# Sheet1.net
KiCad netlist of a schematic drawn in Altium Designer
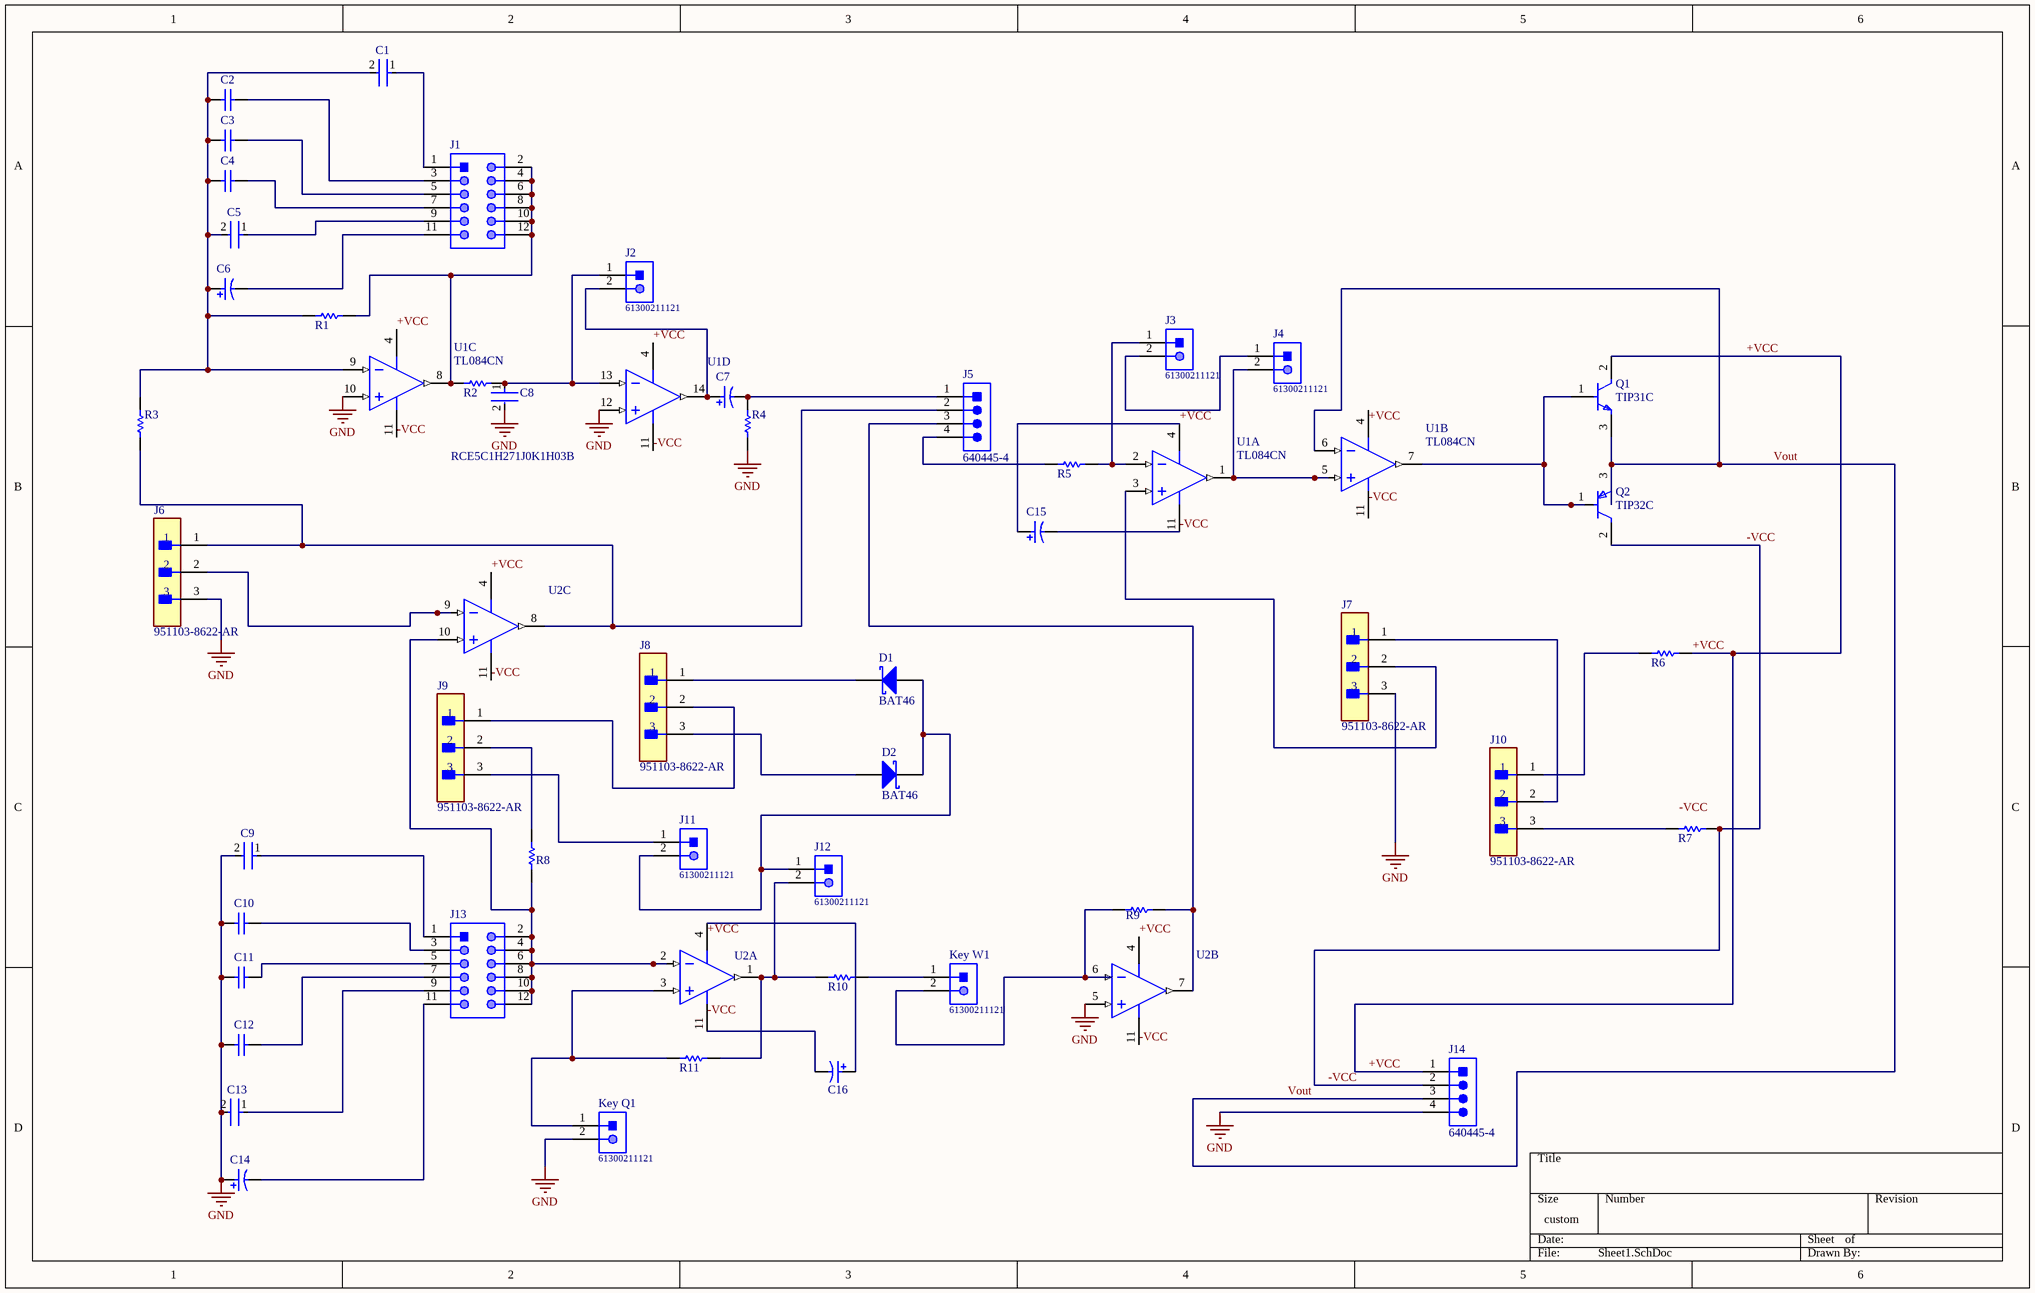
[diagram p0: Sheet1.SchDoc]

(export (version "E")
  (design (tool "Eeschema 10.0.6"))
  (components
    (comp (ref "C1")
      (value "RCE5C1H101J0DBH03A")
      (footprint "FP-RCE0DB-MFG")
      (description "Cap Ceramic 100pF 50V C0G ±5% Radial 2.5mm +125°C Ammo Pack")
      (fields (field (name "TOLERANCE") "5%"))
      (libsource (lib "Altium Content Vault") (part "b4654b650e69147ec39a6b967a45e02"))
    )
    (comp (ref "C2")
      (value "C315C102K1R5TA")
      (footprint "KEMT-C315-THT-2")
      (description "Capacitor, Ceramic, 1000 pF, +/-10 %, 100 V, X7R, -55 to 125 degC, 2-Pin THD, RoHS, Bulk")
      (libsource (lib "Altium Content Vault") (part "CAP-NP-2"))
    )
    (comp (ref "C3")
      (value "C315C103K1R5TA")
      (footprint "KEMT-C315-THT-2")
      (description "Capacitor, Ceramic, 0.01 uF, +/- 10%, 100 V, X7R, -55 to 125 degC, 2-Pin THD, RoHS, Bulk")
      (libsource (lib "Altium Content Vault") (part "CAP-NP-2"))
    )
    (comp (ref "C4")
      (value "C320C104K5R5TA")
      (footprint "CAPR51-254-508X318X736")
      (libsource (lib "Altium Content Vault") (part "CAP-NP-2"))
    )
    (comp (ref "C5")
      (value "K105Z20Y5VF5TL2")
      (footprint "FP-K105Z20Y5VF5TL2-MFG")
      (description "CAP CER 1UF 50V Y5V RADIAL")
      (fields
        (field (name "TOLERANCE") "-20+80%")
        (field (name "OCTOPART") "https://octopart.com/k105z20y5vf5tl2-vishay-39475252")
      )
      (libsource (lib "Altium Content Vault") (part "11868f565c42a9108669ba33697ecf6"))
    )
    (comp (ref "C6")
      (value "ECA1HM100")
      (footprint "CAPPR55-200-1100X500X1200")
      (description "Aluminum Electrolytic Capacitor, 10 uF, +/- 20%, 50 V, -40 to 85 degC, 2-Pin THD, RoHS, Bulk")
      (fields (field (name "MANUFACTURER") "Panasonic") (field (name "TOLERANCE") "20%"))
      (libsource (lib "Altium Content Vault") (part "CAP-P-2"))
    )
    (comp (ref "C7")
      (value "ECA1HM100")
      (footprint "CAPPR55-200-1100X500X1200")
      (description "Aluminum Electrolytic Capacitor, 10 uF, +/- 20%, 50 V, -40 to 85 degC, 2-Pin THD, RoHS, Bulk")
      (fields (field (name "MANUFACTURER") "Panasonic") (field (name "TOLERANCE") "20%"))
      (libsource (lib "Altium Content Vault") (part "CAP-P-2"))
    )
    (comp (ref "C8")
      (value "RCE5C1H271J0K1H03B")
      (footprint "FP-RCE0K1-MFG")
      (description "Cap Ceramic 270pF 50V C0G ±5% Radial 5mm +125°C Automotive Bulk")
      (fields (field (name "TOLERANCE") "5%"))
      (libsource (lib "Altium Content Vault") (part "b4654b650e69147ec39a6b967a45e02"))
    )
    (comp (ref "C9")
      (value "RCE5C1H101J0DBH03A")
      (footprint "FP-RCE0DB-MFG")
      (description "Cap Ceramic 100pF 50V C0G ±5% Radial 2.5mm +125°C Ammo Pack")
      (fields (field (name "TOLERANCE") "5%"))
      (libsource (lib "Altium Content Vault") (part "b4654b650e69147ec39a6b967a45e02"))
    )
    (comp (ref "C10")
      (value "C315C102K1R5TA")
      (footprint "KEMT-C315-THT-2")
      (description "Capacitor, Ceramic, 1000 pF, +/-10 %, 100 V, X7R, -55 to 125 degC, 2-Pin THD, RoHS, Bulk")
      (libsource (lib "Altium Content Vault") (part "CAP-NP-2"))
    )
    (comp (ref "C11")
      (value "C315C103K1R5TA")
      (footprint "KEMT-C315-THT-2")
      (description "Capacitor, Ceramic, 0.01 uF, +/- 10%, 100 V, X7R, -55 to 125 degC, 2-Pin THD, RoHS, Bulk")
      (libsource (lib "Altium Content Vault") (part "CAP-NP-2"))
    )
    (comp (ref "C12")
      (value "C320C104K5R5TA")
      (footprint "CAPR51-254-508X318X736")
      (libsource (lib "Altium Content Vault") (part "CAP-NP-2"))
    )
    (comp (ref "C13")
      (value "K105Z20Y5VF5TL2")
      (footprint "FP-K105Z20Y5VF5TL2-MFG")
      (description "CAP CER 1UF 50V Y5V RADIAL")
      (fields
        (field (name "TOLERANCE") "-20+80%")
        (field (name "OCTOPART") "https://octopart.com/k105z20y5vf5tl2-vishay-39475252")
      )
      (libsource (lib "Altium Content Vault") (part "11868f565c42a9108669ba33697ecf6"))
    )
    (comp (ref "C14")
      (value "ECA1HM100")
      (footprint "CAPPR55-200-1100X500X1200")
      (description "Aluminum Electrolytic Capacitor, 10 uF, +/- 20%, 50 V, -40 to 85 degC, 2-Pin THD, RoHS, Bulk")
      (fields (field (name "MANUFACTURER") "Panasonic") (field (name "TOLERANCE") "20%"))
      (libsource (lib "Altium Content Vault") (part "CAP-P-2"))
    )
    (comp (ref "C15")
      (value "ECA1HM100")
      (footprint "CAPPR55-200-1100X500X1200")
      (description "Aluminum Electrolytic Capacitor, 10 uF, +/- 20%, 50 V, -40 to 85 degC, 2-Pin THD, RoHS, Bulk")
      (fields (field (name "MANUFACTURER") "Panasonic") (field (name "TOLERANCE") "20%"))
      (libsource (lib "Altium Content Vault") (part "CAP-P-2"))
    )
    (comp (ref "C16")
      (value "ECA1HM100")
      (footprint "CAPPR55-200-1100X500X1200")
      (description "Aluminum Electrolytic Capacitor, 10 uF, +/- 20%, 50 V, -40 to 85 degC, 2-Pin THD, RoHS, Bulk")
      (fields (field (name "MANUFACTURER") "Panasonic") (field (name "TOLERANCE") "20%"))
      (libsource (lib "Altium Content Vault") (part "CAP-P-2"))
    )
    (comp (ref "D1")
      (value "BAT46")
      (footprint "STM-DO-35-2")
      (description "Small Signal Schottky Diode, 150 mA, 100 V, -65 to 125 degC, 2-Pin DO-35, RoHS, Tape and Reel")
      (fields (field (name "MANUFACTURER") "STMicroelectronics"))
      (libsource (lib "Altium Content Vault") (part "DSKY-AK-2"))
    )
    (comp (ref "D2")
      (value "BAT46")
      (footprint "STM-DO-35-2")
      (description "Small Signal Schottky Diode, 150 mA, 100 V, -65 to 125 degC, 2-Pin DO-35, RoHS, Tape and Reel")
      (fields (field (name "MANUFACTURER") "STMicroelectronics"))
      (libsource (lib "Altium Content Vault") (part "DSKY-AK-2"))
    )
    (comp (ref "J1")
      (value "61301221021")
      (footprint "61301221021")
      (description "THT Angled Pin Header WR-PHD, Pitch 2.54 mm, Dual Row, 12 pins")
      (fields (field (name "MANUFACTURER") "Wurth Elektronik") (field (name "PUBLISHER") "WurthElektronik"))
      (libsource (lib "Altium Content Vault") (part "WE-CN-2P-M-R12"))
    )
    (comp (ref "J2")
      (value "61300211121")
      (footprint "61300211121")
      (description "THT Vertical Pin Header WR-PHD, Pitch 2.54 mm, Single Row, 2 pins")
      (fields (field (name "MANUFACTURER") "Wurth Elektronik") (field (name "PUBLISHER") "WurthElektronik"))
      (libsource (lib "Altium Content Vault") (part "WE-CN-1P-M-R2"))
    )
    (comp (ref "J3")
      (value "61300211121")
      (footprint "61300211121")
      (description "THT Vertical Pin Header WR-PHD, Pitch 2.54 mm, Single Row, 2 pins")
      (fields (field (name "MANUFACTURER") "Wurth Elektronik") (field (name "PUBLISHER") "WurthElektronik"))
      (libsource (lib "Altium Content Vault") (part "WE-CN-1P-M-R2"))
    )
    (comp (ref "J4")
      (value "61300211121")
      (footprint "61300211121")
      (description "THT Vertical Pin Header WR-PHD, Pitch 2.54 mm, Single Row, 2 pins")
      (fields (field (name "MANUFACTURER") "Wurth Elektronik") (field (name "PUBLISHER") "WurthElektronik"))
      (libsource (lib "Altium Content Vault") (part "WE-CN-1P-M-R2"))
    )
    (comp (ref "J5")
      (value "640445-4")
      (footprint "TECO-640445-4_V")
      (fields (field (name "MANUFACTURER") "TE Connectivity"))
      (libsource (lib "Altium Content Vault") (part "CN-1P-M-R4"))
    )
    (comp (ref "J6")
      (value "951103-8622-AR")
      (footprint "FP-951103-8622-AR-MFG")
      (description "CONN HEADER VERT 3POS 2MM")
      (fields
        (field (name "OCTOPART") "https://octopart.com/951103-8622-ar-3m-14400669")
        (field (name "MANUFACTURER") "3M")
      )
      (libsource (lib "Altium Content Vault") (part "0d3f023dd272f625e17a2be33dea85f"))
    )
    (comp (ref "J7")
      (value "951103-8622-AR")
      (footprint "FP-951103-8622-AR-MFG")
      (description "CONN HEADER VERT 3POS 2MM")
      (fields
        (field (name "OCTOPART") "https://octopart.com/951103-8622-ar-3m-14400669")
        (field (name "MANUFACTURER") "3M")
      )
      (libsource (lib "Altium Content Vault") (part "0d3f023dd272f625e17a2be33dea85f"))
    )
    (comp (ref "J8")
      (value "951103-8622-AR")
      (footprint "FP-951103-8622-AR-MFG")
      (description "CONN HEADER VERT 3POS 2MM")
      (fields
        (field (name "OCTOPART") "https://octopart.com/951103-8622-ar-3m-14400669")
        (field (name "MANUFACTURER") "3M")
      )
      (libsource (lib "Altium Content Vault") (part "0d3f023dd272f625e17a2be33dea85f"))
    )
    (comp (ref "J9")
      (value "951103-8622-AR")
      (footprint "FP-951103-8622-AR-MFG")
      (description "CONN HEADER VERT 3POS 2MM")
      (fields
        (field (name "OCTOPART") "https://octopart.com/951103-8622-ar-3m-14400669")
        (field (name "MANUFACTURER") "3M")
      )
      (libsource (lib "Altium Content Vault") (part "0d3f023dd272f625e17a2be33dea85f"))
    )
    (comp (ref "J10")
      (value "951103-8622-AR")
      (footprint "FP-951103-8622-AR-MFG")
      (description "CONN HEADER VERT 3POS 2MM")
      (fields
        (field (name "OCTOPART") "https://octopart.com/951103-8622-ar-3m-14400669")
        (field (name "MANUFACTURER") "3M")
      )
      (libsource (lib "Altium Content Vault") (part "0d3f023dd272f625e17a2be33dea85f"))
    )
    (comp (ref "J11")
      (value "61300211121")
      (footprint "61300211121")
      (description "THT Vertical Pin Header WR-PHD, Pitch 2.54 mm, Single Row, 2 pins")
      (fields (field (name "MANUFACTURER") "Wurth Elektronik") (field (name "PUBLISHER") "WurthElektronik"))
      (libsource (lib "Altium Content Vault") (part "WE-CN-1P-M-R2"))
    )
    (comp (ref "J12")
      (value "61300211121")
      (footprint "61300211121")
      (description "THT Vertical Pin Header WR-PHD, Pitch 2.54 mm, Single Row, 2 pins")
      (fields (field (name "MANUFACTURER") "Wurth Elektronik") (field (name "PUBLISHER") "WurthElektronik"))
      (libsource (lib "Altium Content Vault") (part "WE-CN-1P-M-R2"))
    )
    (comp (ref "J13")
      (value "61301221021")
      (footprint "61301221021")
      (description "THT Angled Pin Header WR-PHD, Pitch 2.54 mm, Dual Row, 12 pins")
      (fields (field (name "MANUFACTURER") "Wurth Elektronik") (field (name "PUBLISHER") "WurthElektronik"))
      (libsource (lib "Altium Content Vault") (part "WE-CN-2P-M-R12"))
    )
    (comp (ref "J14")
      (value "640445-4")
      (footprint "TECO-640445-4_V")
      (fields (field (name "MANUFACTURER") "TE Connectivity"))
      (libsource (lib "Altium Content Vault") (part "CN-1P-M-R4"))
    )
    (comp (ref "Key Q1")
      (value "61300211121")
      (footprint "61300211121")
      (description "THT Vertical Pin Header WR-PHD, Pitch 2.54 mm, Single Row, 2 pins")
      (fields (field (name "MANUFACTURER") "Wurth Elektronik") (field (name "PUBLISHER") "WurthElektronik"))
      (libsource (lib "Altium Content Vault") (part "WE-CN-1P-M-R2"))
    )
    (comp (ref "Key W1")
      (value "61300211121")
      (footprint "61300211121")
      (description "THT Vertical Pin Header WR-PHD, Pitch 2.54 mm, Single Row, 2 pins")
      (fields (field (name "MANUFACTURER") "Wurth Elektronik") (field (name "PUBLISHER") "WurthElektronik"))
      (libsource (lib "Altium Content Vault") (part "WE-CN-1P-M-R2"))
    )
    (comp (ref "Q1")
      (value "TIP31C")
      (footprint "FP-TO-220-P0A0015988-MFG")
      (description "TRANS NPN 100V 3A TO-220")
      (fields
        (field (name "OCTOPART") "https://octopart.com/tip31c-stmicroelectronics-15555")
        (field (name "MANUFACTURER") "STMicroelectronics")
      )
      (libsource (lib "Altium Content Vault") (part "1c57d9dae74fe2702546667b0e849db"))
    )
    (comp (ref "Q2")
      (value "TIP32C")
      (footprint "FP-TO-220-P0A0015988-MFG")
      (description "TRANS PNP 100V 3A TO-220")
      (fields
        (field (name "MANUFACTURER") "STMicroelectronics")
        (field (name "OCTOPART") "https://octopart.com/tip32c-stmicroelectronics-353617")
      )
      (libsource (lib "Altium Content Vault") (part "802a31d42ca070764d097f06bc9597f"))
    )
    (comp (ref "R1")
      (value "MFR-25FBF52-100K")
      (footprint "RESA60-630X240")
      (description "Axial Resistor, 100 KOhm, +/- 1%, 0.25 W, -55 to 155 degC, 2-Pin THD, RoHS, Bulk")
      (fields (field (name "TOLERANCE") "1%"))
      (libsource (lib "Altium Content Vault") (part "RES-2"))
    )
    (comp (ref "R2")
      (value "MFR-25FBF52-1K")
      (footprint "RESA60-630X240")
      (description "Axial Resistor, 1 KOhm, +/- 1%, 250 mW, -55 to 155 degC, 2-Pin THD, RoHS, Bulk")
      (fields (field (name "TOLERANCE") "1%"))
      (libsource (lib "Altium Content Vault") (part "RES-2"))
    )
    (comp (ref "R3")
      (value "MFR-25FBF52-100K")
      (footprint "RESA60-630X240")
      (description "Axial Resistor, 100 KOhm, +/- 1%, 0.25 W, -55 to 155 degC, 2-Pin THD, RoHS, Bulk")
      (fields (field (name "TOLERANCE") "1%"))
      (libsource (lib "Altium Content Vault") (part "RES-2"))
    )
    (comp (ref "R4")
      (value "MFR-25FBF52-100K")
      (footprint "RESA60-630X240")
      (description "Axial Resistor, 100 KOhm, +/- 1%, 0.25 W, -55 to 155 degC, 2-Pin THD, RoHS, Bulk")
      (fields (field (name "TOLERANCE") "1%"))
      (libsource (lib "Altium Content Vault") (part "RES-2"))
    )
    (comp (ref "R5")
      (value "MFR-25FBF52-100K")
      (footprint "RESA60-630X240")
      (description "Axial Resistor, 100 KOhm, +/- 1%, 0.25 W, -55 to 155 degC, 2-Pin THD, RoHS, Bulk")
      (fields (field (name "TOLERANCE") "1%"))
      (libsource (lib "Altium Content Vault") (part "RES-2"))
    )
    (comp (ref "R6")
      (value "MFR-25FBF52-100K")
      (footprint "RESA60-630X240")
      (description "Axial Resistor, 100 KOhm, +/- 1%, 0.25 W, -55 to 155 degC, 2-Pin THD, RoHS, Bulk")
      (fields (field (name "TOLERANCE") "1%"))
      (libsource (lib "Altium Content Vault") (part "RES-2"))
    )
    (comp (ref "R7")
      (value "MFR-25FBF52-100K")
      (footprint "RESA60-630X240")
      (description "Axial Resistor, 100 KOhm, +/- 1%, 0.25 W, -55 to 155 degC, 2-Pin THD, RoHS, Bulk")
      (fields (field (name "TOLERANCE") "1%"))
      (libsource (lib "Altium Content Vault") (part "RES-2"))
    )
    (comp (ref "R8")
      (value "MFR-25FBF52-1K")
      (footprint "RESA60-630X240")
      (description "Axial Resistor, 1 KOhm, +/- 1%, 250 mW, -55 to 155 degC, 2-Pin THD, RoHS, Bulk")
      (fields (field (name "TOLERANCE") "1%"))
      (libsource (lib "Altium Content Vault") (part "RES-2"))
    )
    (comp (ref "R9")
      (value "MFR-25FBF52-1K")
      (footprint "RESA60-630X240")
      (description "Axial Resistor, 1 KOhm, +/- 1%, 250 mW, -55 to 155 degC, 2-Pin THD, RoHS, Bulk")
      (fields (field (name "TOLERANCE") "1%"))
      (libsource (lib "Altium Content Vault") (part "RES-2"))
    )
    (comp (ref "R10")
      (value "MFR-25FBF52-100K")
      (footprint "RESA60-630X240")
      (description "Axial Resistor, 100 KOhm, +/- 1%, 0.25 W, -55 to 155 degC, 2-Pin THD, RoHS, Bulk")
      (fields (field (name "TOLERANCE") "1%"))
      (libsource (lib "Altium Content Vault") (part "RES-2"))
    )
    (comp (ref "R11")
      (value "MFR-25FBF52-100K")
      (footprint "RESA60-630X240")
      (description "Axial Resistor, 100 KOhm, +/- 1%, 0.25 W, -55 to 155 degC, 2-Pin THD, RoHS, Bulk")
      (fields (field (name "TOLERANCE") "1%"))
      (libsource (lib "Altium Content Vault") (part "RES-2"))
    )
    (comp (ref "U1")
      (value "TL084CN")
      (footprint "N0014A")
      (description "JFET-Input Operational Amplifier, 7 to 36 V, 0 to 70 degC, 14-pin DIP (N14), Pb-Free (RoHS)")
      (fields (field (name "MANUFACTURER") "Texas Instruments"))
      (libsource (lib "Altium Content Vault") (part "TI-TLXX4X_MC3403-X14"))
    )
    (comp (ref "U2")
      (value "TL084CN")
      (footprint "N0014A")
      (description "JFET-Input Operational Amplifier, 7 to 36 V, 0 to 70 degC, 14-pin DIP (N14), Pb-Free (RoHS)")
      (fields (field (name "MANUFACTURER") "Texas Instruments"))
      (libsource (lib "Altium Content Vault") (part "TI-TLXX4X_MC3403-X14"))
    )
  )
  (nets
    (net (code "1") (name "/+VCC") (class "Default")
      (node (ref "C15") (pin "1") (pinfunction "1_1") (pintype "passive"))
      (node (ref "J14") (pin "1") (pinfunction "1_1") (pintype "passive"))
      (node (ref "Q1") (pin "2") (pinfunction "C_2") (pintype "passive"))
      (node (ref "R6") (pin "1") (pinfunction "1_1") (pintype "passive"))
      (node (ref "U1") (pin "4") (pinfunction "VCC+_4") (pintype "power_in"))
      (node (ref "U2") (pin "4") (pinfunction "VCC+_4") (pintype "power_in"))
    )
    (net (code "2") (name "/-VCC") (class "Default")
      (node (ref "C15") (pin "2") (pinfunction "2_2") (pintype "passive"))
      (node (ref "J14") (pin "2") (pinfunction "2_2") (pintype "passive"))
      (node (ref "Q2") (pin "2") (pinfunction "C_2") (pintype "passive"))
      (node (ref "R7") (pin "1") (pinfunction "1_1") (pintype "passive"))
      (node (ref "U1") (pin "11") (pinfunction "VCC-_11") (pintype "power_in"))
      (node (ref "U2") (pin "11") (pinfunction "VCC-_11") (pintype "power_in"))
    )
    (net (code "3") (name "/Vout") (class "Default")
      (node (ref "J14") (pin "3") (pinfunction "3_3") (pintype "passive"))
      (node (ref "Q1") (pin "3") (pinfunction "E_3") (pintype "passive"))
      (node (ref "Q2") (pin "3") (pinfunction "E_3") (pintype "passive"))
      (node (ref "U1") (pin "6") (pinfunction "IN2-_6") (pintype "input"))
    )
    (net (code "4") (name "GND") (class "Default")
      (node (ref "C10") (pin "1") (pinfunction "1_1") (pintype "passive"))
      (node (ref "C11") (pin "1") (pinfunction "1_1") (pintype "passive"))
      (node (ref "C12") (pin "1") (pinfunction "1_1") (pintype "passive"))
      (node (ref "C13") (pin "2") (pinfunction "2_2") (pintype "passive"))
      (node (ref "C14") (pin "1") (pinfunction "1_1") (pintype "passive"))
      (node (ref "C8") (pin "2") (pinfunction "2_2") (pintype "passive"))
      (node (ref "C9") (pin "2") (pinfunction "2_2") (pintype "passive"))
      (node (ref "J14") (pin "4") (pinfunction "4_4") (pintype "passive"))
      (node (ref "J6") (pin "3") (pinfunction "3_3") (pintype "passive"))
      (node (ref "J7") (pin "3") (pinfunction "3_3") (pintype "passive"))
      (node (ref "Key Q1") (pin "2") (pinfunction "2_2") (pintype "passive"))
      (node (ref "R4") (pin "1") (pinfunction "1_1") (pintype "passive"))
      (node (ref "U1") (pin "10") (pinfunction "IN3+_10") (pintype "input"))
      (node (ref "U1") (pin "12") (pinfunction "IN4+_12") (pintype "input"))
      (node (ref "U2") (pin "5") (pinfunction "IN2+_5") (pintype "input"))
    )
    (net (code "5") (name "Net-(C1-Pad1)") (class "Default")
      (node (ref "C1") (pin "1") (pinfunction "1_1") (pintype "passive"))
      (node (ref "J1") (pin "1") (pinfunction "1_1") (pintype "passive"))
    )
    (net (code "6") (name "Net-(C2-Pad2)") (class "Default")
      (node (ref "C2") (pin "2") (pinfunction "2_2") (pintype "passive"))
      (node (ref "J1") (pin "3") (pinfunction "3_3") (pintype "passive"))
    )
    (net (code "7") (name "Net-(C3-Pad2)") (class "Default")
      (node (ref "C3") (pin "2") (pinfunction "2_2") (pintype "passive"))
      (node (ref "J1") (pin "5") (pinfunction "5_5") (pintype "passive"))
    )
    (net (code "8") (name "Net-(C4-Pad2)") (class "Default")
      (node (ref "C4") (pin "2") (pinfunction "2_2") (pintype "passive"))
      (node (ref "J1") (pin "7") (pinfunction "7_7") (pintype "passive"))
    )
    (net (code "9") (name "Net-(C5-Pad1)") (class "Default")
      (node (ref "C5") (pin "1") (pinfunction "1_1") (pintype "passive"))
      (node (ref "J1") (pin "9") (pinfunction "9_9") (pintype "passive"))
    )
    (net (code "10") (name "Net-(C6-Pad2)") (class "Default")
      (node (ref "C6") (pin "2") (pinfunction "2_2") (pintype "passive"))
      (node (ref "J1") (pin "11") (pinfunction "11_11") (pintype "passive"))
    )
    (net (code "11") (name "Net-(C7-Pad2)") (class "Default")
      (node (ref "C7") (pin "2") (pinfunction "2_2") (pintype "passive"))
      (node (ref "J5") (pin "1") (pinfunction "1_1") (pintype "passive"))
      (node (ref "R4") (pin "2") (pinfunction "2_2") (pintype "passive"))
    )
    (net (code "12") (name "Net-(C9-Pad1)") (class "Default")
      (node (ref "C9") (pin "1") (pinfunction "1_1") (pintype "passive"))
      (node (ref "J13") (pin "1") (pinfunction "1_1") (pintype "passive"))
    )
    (net (code "13") (name "Net-(C10-Pad2)") (class "Default")
      (node (ref "C10") (pin "2") (pinfunction "2_2") (pintype "passive"))
      (node (ref "J13") (pin "3") (pinfunction "3_3") (pintype "passive"))
    )
    (net (code "14") (name "Net-(C11-Pad2)") (class "Default")
      (node (ref "C11") (pin "2") (pinfunction "2_2") (pintype "passive"))
      (node (ref "J13") (pin "5") (pinfunction "5_5") (pintype "passive"))
    )
    (net (code "15") (name "Net-(C12-Pad2)") (class "Default")
      (node (ref "C12") (pin "2") (pinfunction "2_2") (pintype "passive"))
      (node (ref "J13") (pin "7") (pinfunction "7_7") (pintype "passive"))
    )
    (net (code "16") (name "Net-(C13-Pad1)") (class "Default")
      (node (ref "C13") (pin "1") (pinfunction "1_1") (pintype "passive"))
      (node (ref "J13") (pin "9") (pinfunction "9_9") (pintype "passive"))
    )
    (net (code "17") (name "Net-(C14-Pad2)") (class "Default")
      (node (ref "C14") (pin "2") (pinfunction "2_2") (pintype "passive"))
      (node (ref "J13") (pin "11") (pinfunction "11_11") (pintype "passive"))
    )
    (net (code "18") (name "Net-(D1-A)") (class "Default")
      (node (ref "D1") (pin "1") (pinfunction "A_1") (pintype "passive"))
      (node (ref "D2") (pin "2") (pinfunction "K_2") (pintype "passive"))
      (node (ref "J11") (pin "2") (pinfunction "2_2") (pintype "passive"))
      (node (ref "J12") (pin "1") (pinfunction "1_1") (pintype "passive"))
    )
    (net (code "19") (name "Net-(D1-K)") (class "Default")
      (node (ref "D1") (pin "2") (pinfunction "K_2") (pintype "passive"))
      (node (ref "J8") (pin "1") (pinfunction "1_1") (pintype "passive"))
    )
    (net (code "20") (name "Net-(D2-A)") (class "Default")
      (node (ref "D2") (pin "1") (pinfunction "A_1") (pintype "passive"))
      (node (ref "J8") (pin "3") (pinfunction "3_3") (pintype "passive"))
    )
    (net (code "21") (name "Net-(J3-Pad2)") (class "Default")
      (node (ref "J3") (pin "2") (pinfunction "2_2") (pintype "passive"))
      (node (ref "J4") (pin "1") (pinfunction "1_1") (pintype "passive"))
    )
    (net (code "22") (name "Net-(J5-Pad4)") (class "Default")
      (node (ref "J5") (pin "4") (pinfunction "4_4") (pintype "passive"))
      (node (ref "R5") (pin "2") (pinfunction "2_2") (pintype "passive"))
    )
    (net (code "23") (name "Net-(J8-Pad2)") (class "Default")
      (node (ref "J8") (pin "2") (pinfunction "2_2") (pintype "passive"))
      (node (ref "J9") (pin "1") (pinfunction "1_1") (pintype "passive"))
    )
    (net (code "24") (name "Net-(J9-Pad2)") (class "Default")
      (node (ref "J9") (pin "2") (pinfunction "2_2") (pintype "passive"))
      (node (ref "R8") (pin "1") (pinfunction "1_1") (pintype "passive"))
    )
    (net (code "25") (name "Net-(J10-Pad1)") (class "Default")
      (node (ref "J10") (pin "1") (pinfunction "1_1") (pintype "passive"))
      (node (ref "R6") (pin "2") (pinfunction "2_2") (pintype "passive"))
    )
    (net (code "26") (name "Net-(J10-Pad2)") (class "Default")
      (node (ref "J10") (pin "2") (pinfunction "2_2") (pintype "passive"))
      (node (ref "J7") (pin "1") (pinfunction "1_1") (pintype "passive"))
    )
    (net (code "27") (name "Net-(J10-Pad3)") (class "Default")
      (node (ref "J10") (pin "3") (pinfunction "3_3") (pintype "passive"))
      (node (ref "R7") (pin "2") (pinfunction "2_2") (pintype "passive"))
    )
    (net (code "28") (name "Net-(J11-Pad1)") (class "Default")
      (node (ref "J11") (pin "1") (pinfunction "1_1") (pintype "passive"))
      (node (ref "J9") (pin "3") (pinfunction "3_3") (pintype "passive"))
    )
    (net (code "29") (name "Net-(Key W1-Pad1)") (class "Default")
      (node (ref "Key W1") (pin "1") (pinfunction "1_1") (pintype "passive"))
      (node (ref "R10") (pin "1") (pinfunction "1_1") (pintype "passive"))
    )
    (net (code "30") (name "Net-(Q1-B)") (class "Default")
      (node (ref "Q1") (pin "1") (pinfunction "B_1") (pintype "passive"))
      (node (ref "Q2") (pin "1") (pinfunction "B_1") (pintype "passive"))
      (node (ref "U1") (pin "7") (pinfunction "OUT2_7") (pintype "output"))
    )
    (net (code "31") (name "Net-(U1A-IN1+)") (class "Default")
      (node (ref "J7") (pin "2") (pinfunction "2_2") (pintype "passive"))
      (node (ref "U1") (pin "3") (pinfunction "IN1+_3") (pintype "input"))
    )
    (net (code "32") (name "Net-(U1A-IN1-)") (class "Default")
      (node (ref "J3") (pin "1") (pinfunction "1_1") (pintype "passive"))
      (node (ref "R5") (pin "1") (pinfunction "1_1") (pintype "passive"))
      (node (ref "U1") (pin "2") (pinfunction "IN1-_2") (pintype "input"))
    )
    (net (code "33") (name "Net-(U1A-OUT1)") (class "Default")
      (node (ref "J4") (pin "2") (pinfunction "2_2") (pintype "passive"))
      (node (ref "U1") (pin "1") (pinfunction "OUT1_1") (pintype "output"))
      (node (ref "U1") (pin "5") (pinfunction "IN2+_5") (pintype "input"))
    )
    (net (code "34") (name "Net-(U1C-IN3-)") (class "Default")
      (node (ref "C1") (pin "2") (pinfunction "2_2") (pintype "passive"))
      (node (ref "C2") (pin "1") (pinfunction "1_1") (pintype "passive"))
      (node (ref "C3") (pin "1") (pinfunction "1_1") (pintype "passive"))
      (node (ref "C4") (pin "1") (pinfunction "1_1") (pintype "passive"))
      (node (ref "C5") (pin "2") (pinfunction "2_2") (pintype "passive"))
      (node (ref "C6") (pin "1") (pinfunction "1_1") (pintype "passive"))
      (node (ref "R1") (pin "2") (pinfunction "2_2") (pintype "passive"))
      (node (ref "R3") (pin "2") (pinfunction "2_2") (pintype "passive"))
      (node (ref "U1") (pin "9") (pinfunction "IN3-_9") (pintype "input"))
    )
    (net (code "35") (name "Net-(U1C-OUT3)") (class "Default")
      (node (ref "J1") (pin "10") (pinfunction "10_10") (pintype "passive"))
      (node (ref "J1") (pin "12") (pinfunction "12_12") (pintype "passive"))
      (node (ref "J1") (pin "2") (pinfunction "2_2") (pintype "passive"))
      (node (ref "J1") (pin "4") (pinfunction "4_4") (pintype "passive"))
      (node (ref "J1") (pin "6") (pinfunction "6_6") (pintype "passive"))
      (node (ref "J1") (pin "8") (pinfunction "8_8") (pintype "passive"))
      (node (ref "R1") (pin "1") (pinfunction "1_1") (pintype "passive"))
      (node (ref "R2") (pin "2") (pinfunction "2_2") (pintype "passive"))
      (node (ref "U1") (pin "8") (pinfunction "OUT3_8") (pintype "output"))
    )
    (net (code "36") (name "Net-(U1D-IN4-)") (class "Default")
      (node (ref "C8") (pin "1") (pinfunction "1_1") (pintype "passive"))
      (node (ref "J2") (pin "1") (pinfunction "1_1") (pintype "passive"))
      (node (ref "R2") (pin "1") (pinfunction "1_1") (pintype "passive"))
      (node (ref "U1") (pin "13") (pinfunction "IN4-_13") (pintype "input"))
    )
    (net (code "37") (name "Net-(U1D-OUT4)") (class "Default")
      (node (ref "C7") (pin "1") (pinfunction "1_1") (pintype "passive"))
      (node (ref "J2") (pin "2") (pinfunction "2_2") (pintype "passive"))
      (node (ref "U1") (pin "14") (pinfunction "OUT4_14") (pintype "output"))
    )
    (net (code "38") (name "Net-(U2A-IN1+)") (class "Default")
      (node (ref "Key Q1") (pin "1") (pinfunction "1_1") (pintype "passive"))
      (node (ref "R11") (pin "2") (pinfunction "2_2") (pintype "passive"))
      (node (ref "U2") (pin "3") (pinfunction "IN1+_3") (pintype "input"))
    )
    (net (code "39") (name "Net-(U2A-IN1-)") (class "Default")
      (node (ref "J13") (pin "10") (pinfunction "10_10") (pintype "passive"))
      (node (ref "J13") (pin "12") (pinfunction "12_12") (pintype "passive"))
      (node (ref "J13") (pin "2") (pinfunction "2_2") (pintype "passive"))
      (node (ref "J13") (pin "4") (pinfunction "4_4") (pintype "passive"))
      (node (ref "J13") (pin "6") (pinfunction "6_6") (pintype "passive"))
      (node (ref "J13") (pin "8") (pinfunction "8_8") (pintype "passive"))
      (node (ref "R8") (pin "2") (pinfunction "2_2") (pintype "passive"))
      (node (ref "U2") (pin "10") (pinfunction "IN3+_10") (pintype "input"))
      (node (ref "U2") (pin "2") (pinfunction "IN1-_2") (pintype "input"))
    )
    (net (code "40") (name "Net-(U2A-OUT1)") (class "Default")
      (node (ref "J12") (pin "2") (pinfunction "2_2") (pintype "passive"))
      (node (ref "R10") (pin "2") (pinfunction "2_2") (pintype "passive"))
      (node (ref "R11") (pin "1") (pinfunction "1_1") (pintype "passive"))
      (node (ref "U2") (pin "1") (pinfunction "OUT1_1") (pintype "output"))
    )
    (net (code "41") (name "Net-(U2A-VCC+)") (class "Default")
      (node (ref "C16") (pin "1") (pinfunction "1_1") (pintype "passive"))
      (node (ref "U2") (pin "4") (pinfunction "VCC+_4") (pintype "power_in"))
    )
    (net (code "42") (name "Net-(U2A-VCC-)") (class "Default")
      (node (ref "C16") (pin "2") (pinfunction "2_2") (pintype "passive"))
      (node (ref "U2") (pin "11") (pinfunction "VCC-_11") (pintype "power_in"))
    )
    (net (code "43") (name "Net-(U2B-IN2-)") (class "Default")
      (node (ref "Key W1") (pin "2") (pinfunction "2_2") (pintype "passive"))
      (node (ref "R9") (pin "1") (pinfunction "1_1") (pintype "passive"))
      (node (ref "U2") (pin "6") (pinfunction "IN2-_6") (pintype "input"))
    )
    (net (code "44") (name "Net-(U2B-OUT2)") (class "Default")
      (node (ref "J5") (pin "3") (pinfunction "3_3") (pintype "passive"))
      (node (ref "R9") (pin "2") (pinfunction "2_2") (pintype "passive"))
      (node (ref "U2") (pin "7") (pinfunction "OUT2_7") (pintype "output"))
    )
    (net (code "45") (name "Net-(U2C-IN3-)") (class "Default")
      (node (ref "J6") (pin "2") (pinfunction "2_2") (pintype "passive"))
      (node (ref "U2") (pin "9") (pinfunction "IN3-_9") (pintype "input"))
    )
    (net (code "46") (name "Net-(U2C-OUT3)") (class "Default")
      (node (ref "J5") (pin "2") (pinfunction "2_2") (pintype "passive"))
      (node (ref "J6") (pin "1") (pinfunction "1_1") (pintype "passive"))
      (node (ref "R3") (pin "1") (pinfunction "1_1") (pintype "passive"))
      (node (ref "U2") (pin "8") (pinfunction "OUT3_8") (pintype "output"))
    )
    (net (code "47") (name "unconnected-(U1B-VCC+-Pad4)") (class "Default")
      (node (ref "U1") (pin "4") (pinfunction "VCC+_4") (pintype "power_in"))
    )
    (net (code "48") (name "unconnected-(U1B-VCC--Pad11)") (class "Default")
      (node (ref "U1") (pin "11") (pinfunction "VCC-_11") (pintype "power_in"))
    )
  )
)
